# 15-12power.net
KiCad netlist of a schematic drawn in Altium Designer
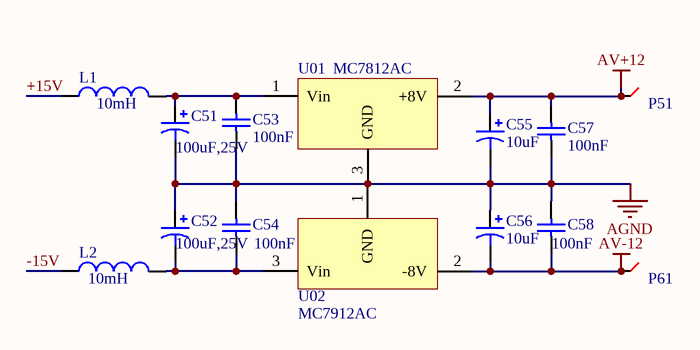
[diagram p0: 15-12power.SchDoc]

(export (version "E")
  (design (tool "Eeschema 10.0.6"))
  (components
    (comp (ref "C51")
      (value "100uF,25V")
      (footprint "CAPC2012L")
      (description "Polarized Capacitor (Surface Mount)")
      (fields (field (name "Comment") "Cap Pol3") (field (name "PUBLISHER") "Altium Limited"))
      (libsource (lib "Miscellaneous Devices") (part "Cap Pol3"))
    )
    (comp (ref "C52")
      (value "100uF,25V")
      (footprint "CAPC2012L")
      (description "Polarized Capacitor (Surface Mount)")
      (fields (field (name "Comment") "Cap Pol3") (field (name "PUBLISHER") "Altium Limited"))
      (libsource (lib "Miscellaneous Devices") (part "Cap Pol3"))
    )
    (comp (ref "C53")
      (value "100nF")
      (footprint "0805-2")
      (description "Capacitor")
      (fields (field (name "Comment") "Cap") (field (name "PUBLISHER") "Altium Limited"))
      (libsource (lib "Miscellaneous Devices") (part "Cap"))
    )
    (comp (ref "C54")
      (value "100nF")
      (footprint "0805-2")
      (description "Capacitor")
      (fields (field (name "Comment") "Cap") (field (name "PUBLISHER") "Altium Limited"))
      (libsource (lib "Miscellaneous Devices") (part "Cap"))
    )
    (comp (ref "C55")
      (value "10uF")
      (footprint "RB7.6-15")
      (description "Polarized Capacitor (Radial)")
      (fields (field (name "Comment") "Cap Pol1") (field (name "PUBLISHER") "Altium Limited"))
      (libsource (lib "Miscellaneous Devices") (part "Cap Pol1"))
    )
    (comp (ref "C56")
      (value "10uF")
      (footprint "RB7.6-15")
      (description "Polarized Capacitor (Radial)")
      (fields (field (name "Comment") "Cap Pol1") (field (name "PUBLISHER") "Altium Limited"))
      (libsource (lib "Miscellaneous Devices") (part "Cap Pol1"))
    )
    (comp (ref "C57")
      (value "100nF")
      (footprint "0805-2")
      (description "Capacitor")
      (fields (field (name "Comment") "Cap") (field (name "PUBLISHER") "Altium Limited"))
      (libsource (lib "Miscellaneous Devices") (part "Cap"))
    )
    (comp (ref "C58")
      (value "100nF")
      (footprint "0805-2")
      (description "Capacitor")
      (fields (field (name "Comment") "Cap") (field (name "PUBLISHER") "Altium Limited"))
      (libsource (lib "Miscellaneous Devices") (part "Cap"))
    )
    (comp (ref "L1")
      (value "10mH")
      (footprint "INDC1005AL")
      (description "Inductor")
      (fields (field (name "PUBLISHER") "Altium Limited"))
      (libsource (lib "Miscellaneous Devices") (part "Inductor"))
    )
    (comp (ref "L2")
      (value "10mH")
      (footprint "INDC1005AL")
      (description "Inductor")
      (fields (field (name "PUBLISHER") "Altium Limited"))
      (libsource (lib "Miscellaneous Devices") (part "Inductor"))
    )
    (comp (ref "P51") (value "测试点") (footprint "Text_PAD") (libsource (lib "MY device0") (part "测试点")))
    (comp (ref "P61") (value "测试点") (footprint "Text_PAD") (libsource (lib "MY device0") (part "测试点")))
    (comp (ref "U01") (value "MC7812AC") (footprint "7812") (libsource (lib "MY device0") (part "MC7808K")))
    (comp (ref "U02") (value "MC7912AC") (footprint "7912") (libsource (lib "MY device0") (part "MC7908K")))
  )
  (nets
    (net (code "1") (name "/+15V") (class "Default")
      (node (ref "L1") (pin "1") (pinfunction "1_1") (pintype "passive"))
    )
    (net (code "2") (name "/-15V") (class "Default")
      (node (ref "L2") (pin "1") (pinfunction "1_1") (pintype "passive"))
    )
    (net (code "3") (name "AGND") (class "Default")
      (node (ref "C51") (pin "2") (pinfunction "2_2") (pintype "passive"))
      (node (ref "C52") (pin "1") (pinfunction "1_1") (pintype "passive"))
      (node (ref "C53") (pin "1") (pinfunction "1_1") (pintype "passive"))
      (node (ref "C54") (pin "2") (pinfunction "2_2") (pintype "passive"))
      (node (ref "C55") (pin "2") (pinfunction "2_2") (pintype "passive"))
      (node (ref "C56") (pin "1") (pinfunction "1_1") (pintype "passive"))
      (node (ref "C57") (pin "1") (pinfunction "1_1") (pintype "passive"))
      (node (ref "C58") (pin "2") (pinfunction "2_2") (pintype "passive"))
      (node (ref "U01") (pin "3") (pinfunction "GND_3") (pintype "passive"))
      (node (ref "U02") (pin "1") (pinfunction "GND_1") (pintype "passive"))
    )
    (net (code "4") (name "AV+12") (class "Default")
      (node (ref "C55") (pin "1") (pinfunction "1_1") (pintype "passive"))
      (node (ref "C57") (pin "2") (pinfunction "2_2") (pintype "passive"))
      (node (ref "P51") (pin "A5") (pinfunction "0_A5") (pintype "passive"))
      (node (ref "U01") (pin "2") (pinfunction "+8V_2") (pintype "passive"))
    )
    (net (code "5") (name "AV-12") (class "Default")
      (node (ref "C56") (pin "2") (pinfunction "2_2") (pintype "passive"))
      (node (ref "C58") (pin "1") (pinfunction "1_1") (pintype "passive"))
      (node (ref "P61") (pin "A5") (pinfunction "0_A5") (pintype "passive"))
      (node (ref "U02") (pin "2") (pinfunction "-8V_2") (pintype "passive"))
    )
    (net (code "6") (name "Net-(U01-Vin)") (class "Default")
      (node (ref "C51") (pin "1") (pinfunction "1_1") (pintype "passive"))
      (node (ref "C53") (pin "2") (pinfunction "2_2") (pintype "passive"))
      (node (ref "L1") (pin "2") (pinfunction "2_2") (pintype "passive"))
      (node (ref "U01") (pin "1") (pinfunction "Vin_1") (pintype "passive"))
    )
    (net (code "7") (name "Net-(U02-Vin)") (class "Default")
      (node (ref "C52") (pin "2") (pinfunction "2_2") (pintype "passive"))
      (node (ref "C54") (pin "1") (pinfunction "1_1") (pintype "passive"))
      (node (ref "L2") (pin "2") (pinfunction "2_2") (pintype "passive"))
      (node (ref "U02") (pin "3") (pinfunction "Vin_3") (pintype "passive"))
    )
  )
)
